# harduino0_1.net
KiCad netlist of a schematic drawn in EAGLE
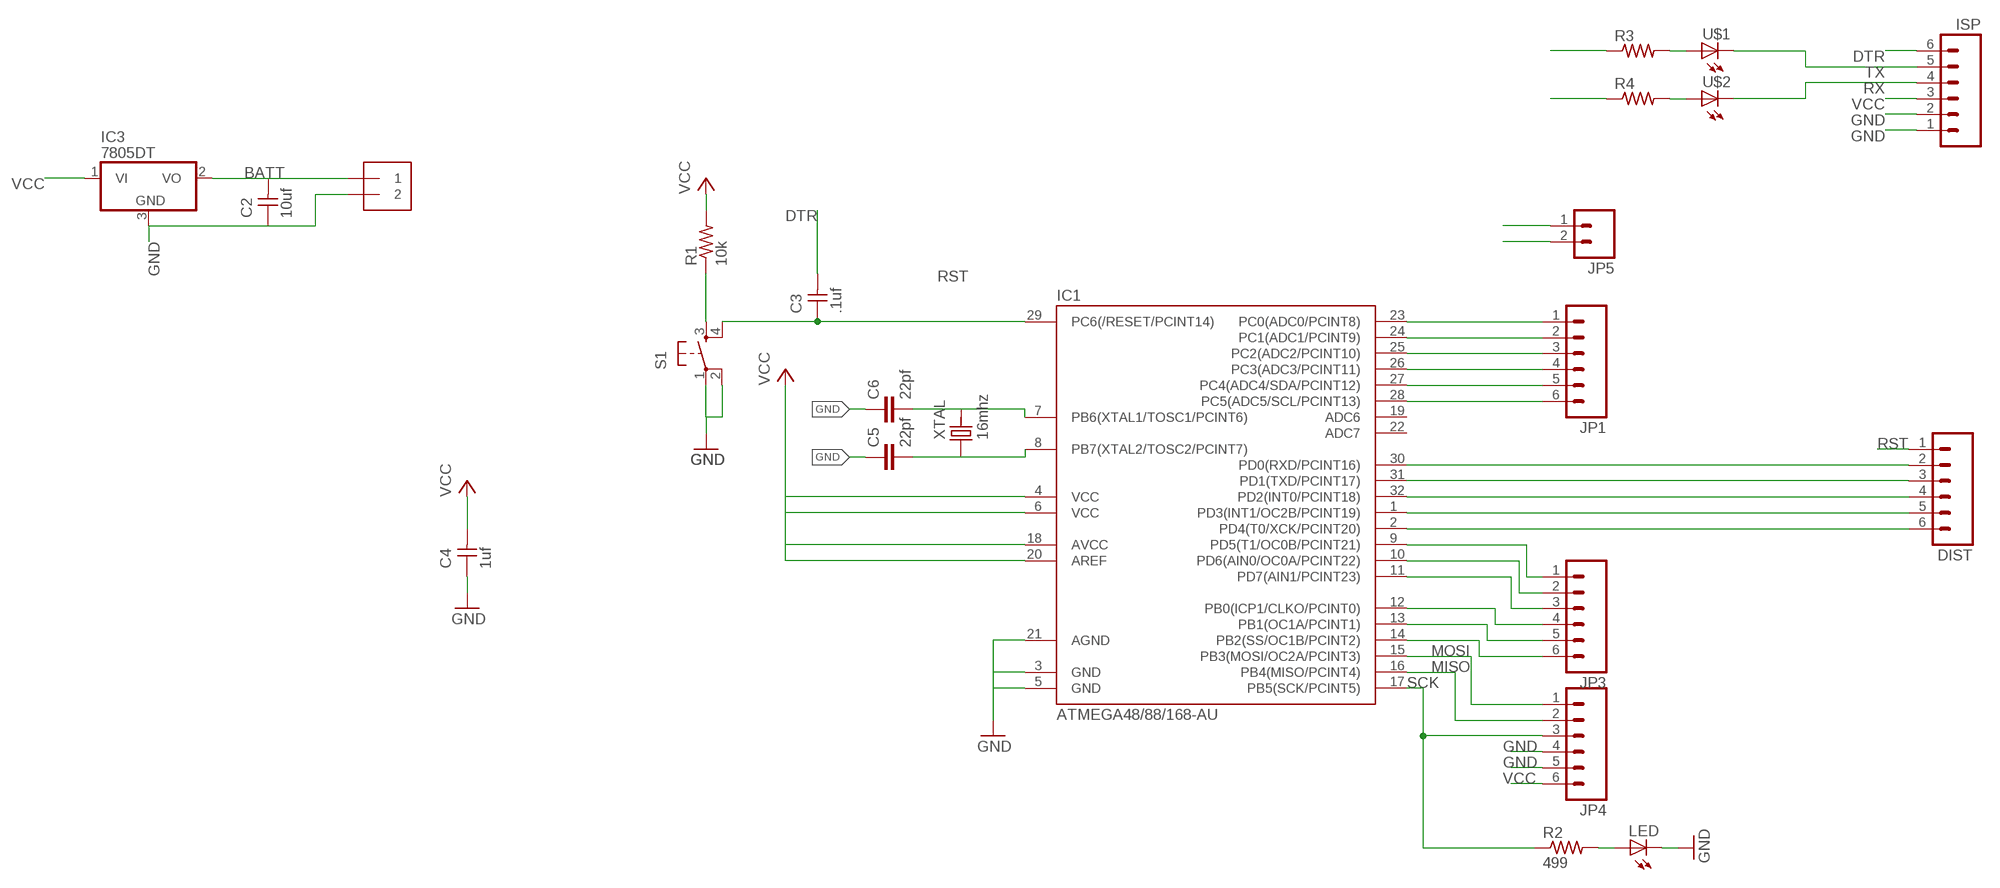
[diagram p0: schematic, sheet 1]

(export (version "E")
  (design (tool "Eeschema 10.0.6"))
  (components
    (comp (ref "C2")
      (value "10uf")
      (footprint "eagle-import:1206")
      (libsource (lib "eagle-import") (part "UNPOLARIZED_CAPACITOR1206"))
    )
    (comp (ref "C3")
      (value ".1uf")
      (footprint "eagle-import:1206")
      (libsource (lib "eagle-import") (part "UNPOLARIZED_CAPACITOR1206"))
    )
    (comp (ref "C4")
      (value "1uf")
      (footprint "eagle-import:1206")
      (libsource (lib "eagle-import") (part "UNPOLARIZED_CAPACITOR1206"))
    )
    (comp (ref "C5")
      (value "22pf")
      (footprint "eagle-import:1206")
      (libsource (lib "eagle-import") (part "CAP1206"))
    )
    (comp (ref "C6")
      (value "22pf")
      (footprint "eagle-import:1206")
      (libsource (lib "eagle-import") (part "CAP1206"))
    )
    (comp (ref "DIST")
      (value "M06LONGPADS")
      (footprint "eagle-import:1X06_LONGPADS")
      (libsource (lib "eagle-import") (part "M06LONGPADS"))
    )
    (comp (ref "IC1")
      (value "ATMEGA48/88/168-AU")
      (footprint "eagle-import:TQFP32-08")
      (libsource (lib "eagle-import") (part "ATMEGA48/88/168-AU"))
    )
    (comp (ref "IC3")
      (value "7805DT")
      (footprint "eagle-import:TO252")
      (libsource (lib "eagle-import") (part "78DT05"))
    )
    (comp (ref "ISP")
      (value "M06SMD")
      (footprint "eagle-import:1X06-SMD")
      (libsource (lib "eagle-import") (part "SparkFun_M06SMD"))
    )
    (comp (ref "J1")
      (value "1X2-3.5MM")
      (footprint "eagle-import:3.5MMTERM")
      (libsource (lib "eagle-import") (part "1X2-3.5MM"))
    )
    (comp (ref "JP1")
      (value "M06LONGPADS")
      (footprint "eagle-import:1X06_LONGPADS")
      (libsource (lib "eagle-import") (part "M06LONGPADS"))
    )
    (comp (ref "JP3")
      (value "M06LONGPADS")
      (footprint "eagle-import:1X06_LONGPADS")
      (libsource (lib "eagle-import") (part "M06LONGPADS"))
    )
    (comp (ref "JP4")
      (value "M06LONGPADS")
      (footprint "eagle-import:1X06_LONGPADS")
      (libsource (lib "eagle-import") (part "M06LONGPADS"))
    )
    (comp (ref "JP5")
      (value "M02")
      (footprint "eagle-import:1X02_LONGPADS")
      (libsource (lib "eagle-import") (part "M02"))
    )
    (comp (ref "LED")
      (value "LED1206")
      (footprint "eagle-import:1206")
      (libsource (lib "eagle-import") (part "ng_LED1206"))
    )
    (comp (ref "R1")
      (value "10k")
      (footprint "eagle-import:1206")
      (libsource (lib "eagle-import") (part "ng_RESISTOR1206"))
    )
    (comp (ref "R2")
      (value "499")
      (footprint "eagle-import:1206")
      (libsource (lib "eagle-import") (part "ng_RESISTOR1206"))
    )
    (comp (ref "R3")
      (value "RESISTOR1206")
      (footprint "eagle-import:1206")
      (libsource (lib "eagle-import") (part "RESISTOR1206"))
    )
    (comp (ref "R4")
      (value "RESISTOR1206")
      (footprint "eagle-import:1206")
      (libsource (lib "eagle-import") (part "RESISTOR1206"))
    )
    (comp (ref "S1")
      (value "6MM_SWITCH6MM_SWITCH")
      (footprint "eagle-import:6MM_SWITCH")
      (libsource (lib "eagle-import") (part "6MM_SWITCH6MM_SWITCH"))
    )
    (comp (ref "U$1")
      (value "LED1206")
      (footprint "eagle-import:1206")
      (libsource (lib "eagle-import") (part "LED1206"))
    )
    (comp (ref "U$2")
      (value "LED1206")
      (footprint "eagle-import:1206")
      (libsource (lib "eagle-import") (part "LED1206"))
    )
    (comp (ref "XTAL")
      (value "16mhz")
      (footprint "eagle-import:CS10")
      (libsource (lib "eagle-import") (part "CRYSTALCS10"))
    )
  )
  (nets
    (net (code "1") (name "/BATT") (class "Default")
      (node (ref "C2") (pin "2") (pinfunction "2_2") (pintype "passive"))
      (node (ref "IC3") (pin "2") (pinfunction "VO_2") (pintype "passive"))
      (node (ref "J1") (pin "1") (pinfunction "1_1") (pintype "passive"))
    )
    (net (code "2") (name "/DTR") (class "Default")
      (node (ref "C3") (pin "2") (pinfunction "2_2") (pintype "passive"))
      (node (ref "ISP") (pin "6") (pinfunction "6_6") (pintype "passive"))
    )
    (net (code "3") (name "/MISO") (class "Default")
      (node (ref "IC1") (pin "16") (pinfunction "PB4(MISO/PCINT4)_16") (pintype "bidirectional"))
      (node (ref "JP4") (pin "2") (pinfunction "2_2") (pintype "passive"))
    )
    (net (code "4") (name "/MOSI") (class "Default")
      (node (ref "IC1") (pin "15") (pinfunction "PB3(MOSI/OC2A/PCINT3)_15") (pintype "bidirectional"))
      (node (ref "JP4") (pin "1") (pinfunction "1_1") (pintype "passive"))
    )
    (net (code "5") (name "/N$18") (class "Default")
      (node (ref "DIST") (pin "2") (pinfunction "2_2") (pintype "passive"))
      (node (ref "IC1") (pin "30") (pinfunction "PD0(RXD/PCINT16)_30") (pintype "bidirectional"))
      (node (ref "R4") (pin "1") (pinfunction "1_1") (pintype "passive"))
    )
    (net (code "6") (name "/N$24") (class "Default")
      (node (ref "DIST") (pin "3") (pinfunction "3_3") (pintype "passive"))
      (node (ref "IC1") (pin "31") (pinfunction "PD1(TXD/PCINT17)_31") (pintype "bidirectional"))
      (node (ref "R3") (pin "1") (pinfunction "1_1") (pintype "passive"))
    )
    (net (code "7") (name "/RST") (class "Default")
      (node (ref "C3") (pin "1") (pinfunction "1_1") (pintype "passive"))
      (node (ref "DIST") (pin "1") (pinfunction "1_1") (pintype "passive"))
      (node (ref "IC1") (pin "29") (pinfunction "PC6(/RESET/PCINT14)_29") (pintype "bidirectional"))
      (node (ref "S1") (pin "4") (pinfunction "S1_4") (pintype "passive"))
    )
    (net (code "8") (name "/RX") (class "Default")
      (node (ref "ISP") (pin "4") (pinfunction "4_4") (pintype "passive"))
      (node (ref "U$2") (pin "2") (pinfunction "C_2") (pintype "passive"))
    )
    (net (code "9") (name "/SCK") (class "Default")
      (node (ref "IC1") (pin "17") (pinfunction "PB5(SCK/PCINT5)_17") (pintype "bidirectional"))
      (node (ref "JP4") (pin "3") (pinfunction "3_3") (pintype "passive"))
      (node (ref "R2") (pin "1") (pinfunction "1_1") (pintype "passive"))
    )
    (net (code "10") (name "/TX") (class "Default")
      (node (ref "ISP") (pin "5") (pinfunction "5_5") (pintype "passive"))
      (node (ref "U$1") (pin "2") (pinfunction "C_2") (pintype "passive"))
    )
    (net (code "11") (name "GND") (class "Default")
      (node (ref "C2") (pin "1") (pinfunction "1_1") (pintype "passive"))
      (node (ref "C4") (pin "1") (pinfunction "1_1") (pintype "passive"))
      (node (ref "C5") (pin "1") (pinfunction "1_1") (pintype "passive"))
      (node (ref "C6") (pin "1") (pinfunction "1_1") (pintype "passive"))
      (node (ref "IC1") (pin "21") (pinfunction "AGND_21") (pintype "power_in"))
      (node (ref "IC1") (pin "3") (pinfunction "GND_3") (pintype "power_in"))
      (node (ref "IC1") (pin "5") (pinfunction "GND_5") (pintype "power_in"))
      (node (ref "IC3") (pin "3") (pinfunction "GND_3") (pintype "passive"))
      (node (ref "ISP") (pin "1") (pinfunction "1_1") (pintype "passive"))
      (node (ref "ISP") (pin "2") (pinfunction "2_2") (pintype "passive"))
      (node (ref "J1") (pin "2") (pinfunction "2_2") (pintype "passive"))
      (node (ref "JP4") (pin "4") (pinfunction "4_4") (pintype "passive"))
      (node (ref "JP4") (pin "5") (pinfunction "5_5") (pintype "passive"))
      (node (ref "JP5") (pin "1") (pinfunction "1_1") (pintype "passive"))
      (node (ref "LED") (pin "2") (pinfunction "C_2") (pintype "passive"))
      (node (ref "S1") (pin "1") (pinfunction "P_1") (pintype "passive"))
      (node (ref "S1") (pin "2") (pinfunction "P1_2") (pintype "passive"))
    )
    (net (code "12") (name "Net-(IC1-PB0(ICP1{slash}CLKO{slash}PCINT0))") (class "Default")
      (node (ref "IC1") (pin "12") (pinfunction "PB0(ICP1/CLKO/PCINT0)_12") (pintype "bidirectional"))
      (node (ref "JP3") (pin "4") (pinfunction "4_4") (pintype "passive"))
    )
    (net (code "13") (name "Net-(IC1-PB1(OC1A{slash}PCINT1))") (class "Default")
      (node (ref "IC1") (pin "13") (pinfunction "PB1(OC1A/PCINT1)_13") (pintype "bidirectional"))
      (node (ref "JP3") (pin "5") (pinfunction "5_5") (pintype "passive"))
    )
    (net (code "14") (name "Net-(IC1-PB2(SS{slash}OC1B{slash}PCINT2))") (class "Default")
      (node (ref "IC1") (pin "14") (pinfunction "PB2(SS/OC1B/PCINT2)_14") (pintype "bidirectional"))
      (node (ref "JP3") (pin "6") (pinfunction "6_6") (pintype "passive"))
    )
    (net (code "15") (name "Net-(IC1-PB6(XTAL1{slash}TOSC1{slash}PCINT6))") (class "Default")
      (node (ref "C6") (pin "2") (pinfunction "2_2") (pintype "passive"))
      (node (ref "IC1") (pin "7") (pinfunction "PB6(XTAL1/TOSC1/PCINT6)_7") (pintype "bidirectional"))
      (node (ref "XTAL") (pin "P$2") (pinfunction "2_P$2") (pintype "passive"))
    )
    (net (code "16") (name "Net-(IC1-PB7(XTAL2{slash}TOSC2{slash}PCINT7))") (class "Default")
      (node (ref "C5") (pin "2") (pinfunction "2_2") (pintype "passive"))
      (node (ref "IC1") (pin "8") (pinfunction "PB7(XTAL2/TOSC2/PCINT7)_8") (pintype "bidirectional"))
      (node (ref "XTAL") (pin "P$1") (pinfunction "1_P$1") (pintype "passive"))
    )
    (net (code "17") (name "Net-(IC1-PC0(ADC0{slash}PCINT8))") (class "Default")
      (node (ref "IC1") (pin "23") (pinfunction "PC0(ADC0/PCINT8)_23") (pintype "bidirectional"))
      (node (ref "JP1") (pin "1") (pinfunction "1_1") (pintype "passive"))
    )
    (net (code "18") (name "Net-(IC1-PC1(ADC1{slash}PCINT9))") (class "Default")
      (node (ref "IC1") (pin "24") (pinfunction "PC1(ADC1/PCINT9)_24") (pintype "bidirectional"))
      (node (ref "JP1") (pin "2") (pinfunction "2_2") (pintype "passive"))
    )
    (net (code "19") (name "Net-(IC1-PC2(ADC2{slash}PCINT10))") (class "Default")
      (node (ref "IC1") (pin "25") (pinfunction "PC2(ADC2/PCINT10)_25") (pintype "bidirectional"))
      (node (ref "JP1") (pin "3") (pinfunction "3_3") (pintype "passive"))
    )
    (net (code "20") (name "Net-(IC1-PC3(ADC3{slash}PCINT11))") (class "Default")
      (node (ref "IC1") (pin "26") (pinfunction "PC3(ADC3/PCINT11)_26") (pintype "bidirectional"))
      (node (ref "JP1") (pin "4") (pinfunction "4_4") (pintype "passive"))
    )
    (net (code "21") (name "Net-(IC1-PC4(ADC4{slash}SDA{slash}PCINT12))") (class "Default")
      (node (ref "IC1") (pin "27") (pinfunction "PC4(ADC4/SDA/PCINT12)_27") (pintype "bidirectional"))
      (node (ref "JP1") (pin "5") (pinfunction "5_5") (pintype "passive"))
    )
    (net (code "22") (name "Net-(IC1-PC5(ADC5{slash}SCL{slash}PCINT13))") (class "Default")
      (node (ref "IC1") (pin "28") (pinfunction "PC5(ADC5/SCL/PCINT13)_28") (pintype "bidirectional"))
      (node (ref "JP1") (pin "6") (pinfunction "6_6") (pintype "passive"))
    )
    (net (code "23") (name "Net-(IC1-PD2(INT0{slash}PCINT18))") (class "Default")
      (node (ref "DIST") (pin "4") (pinfunction "4_4") (pintype "passive"))
      (node (ref "IC1") (pin "32") (pinfunction "PD2(INT0/PCINT18)_32") (pintype "bidirectional"))
    )
    (net (code "24") (name "Net-(IC1-PD3(INT1{slash}OC2B{slash}PCINT19))") (class "Default")
      (node (ref "DIST") (pin "5") (pinfunction "5_5") (pintype "passive"))
      (node (ref "IC1") (pin "1") (pinfunction "PD3(INT1/OC2B/PCINT19)_1") (pintype "bidirectional"))
    )
    (net (code "25") (name "Net-(IC1-PD4(T0{slash}XCK{slash}PCINT20))") (class "Default")
      (node (ref "DIST") (pin "6") (pinfunction "6_6") (pintype "passive"))
      (node (ref "IC1") (pin "2") (pinfunction "PD4(T0/XCK/PCINT20)_2") (pintype "bidirectional"))
    )
    (net (code "26") (name "Net-(IC1-PD5(T1{slash}OC0B{slash}PCINT21))") (class "Default")
      (node (ref "IC1") (pin "9") (pinfunction "PD5(T1/OC0B/PCINT21)_9") (pintype "bidirectional"))
      (node (ref "JP3") (pin "1") (pinfunction "1_1") (pintype "passive"))
    )
    (net (code "27") (name "Net-(IC1-PD6(AIN0{slash}OC0A{slash}PCINT22))") (class "Default")
      (node (ref "IC1") (pin "10") (pinfunction "PD6(AIN0/OC0A/PCINT22)_10") (pintype "bidirectional"))
      (node (ref "JP3") (pin "2") (pinfunction "2_2") (pintype "passive"))
    )
    (net (code "28") (name "Net-(IC1-PD7(AIN1{slash}PCINT23))") (class "Default")
      (node (ref "IC1") (pin "11") (pinfunction "PD7(AIN1/PCINT23)_11") (pintype "bidirectional"))
      (node (ref "JP3") (pin "3") (pinfunction "3_3") (pintype "passive"))
    )
    (net (code "29") (name "Net-(LED-A)") (class "Default")
      (node (ref "LED") (pin "1") (pinfunction "A_1") (pintype "passive"))
      (node (ref "R2") (pin "2") (pinfunction "2_2") (pintype "passive"))
    )
    (net (code "30") (name "Net-(S1-S)") (class "Default")
      (node (ref "R1") (pin "1") (pinfunction "1_1") (pintype "passive"))
      (node (ref "S1") (pin "3") (pinfunction "S_3") (pintype "passive"))
    )
    (net (code "31") (name "Net-(U$1-A)") (class "Default")
      (node (ref "R3") (pin "2") (pinfunction "2_2") (pintype "passive"))
      (node (ref "U$1") (pin "1") (pinfunction "A_1") (pintype "passive"))
    )
    (net (code "32") (name "Net-(U$2-A)") (class "Default")
      (node (ref "R4") (pin "2") (pinfunction "2_2") (pintype "passive"))
      (node (ref "U$2") (pin "1") (pinfunction "A_1") (pintype "passive"))
    )
    (net (code "33") (name "VCC") (class "Default")
      (node (ref "C4") (pin "2") (pinfunction "2_2") (pintype "passive"))
      (node (ref "IC1") (pin "18") (pinfunction "AVCC_18") (pintype "passive"))
      (node (ref "IC1") (pin "20") (pinfunction "AREF_20") (pintype "passive"))
      (node (ref "IC1") (pin "4") (pinfunction "VCC_4") (pintype "power_in"))
      (node (ref "IC1") (pin "6") (pinfunction "VCC_6") (pintype "power_in"))
      (node (ref "IC3") (pin "1") (pinfunction "VI_1") (pintype "input"))
      (node (ref "ISP") (pin "3") (pinfunction "3_3") (pintype "passive"))
      (node (ref "JP4") (pin "6") (pinfunction "6_6") (pintype "passive"))
      (node (ref "JP5") (pin "2") (pinfunction "2_2") (pintype "passive"))
      (node (ref "R1") (pin "2") (pinfunction "2_2") (pintype "passive"))
    )
    (net (code "34") (name "unconnected-(IC1-ADC6-Pad19)") (class "Default")
      (node (ref "IC1") (pin "19") (pinfunction "ADC6_19") (pintype "passive"))
    )
    (net (code "35") (name "unconnected-(IC1-ADC7-Pad22)") (class "Default")
      (node (ref "IC1") (pin "22") (pinfunction "ADC7_22") (pintype "passive"))
    )
  )
)
